# main_16.net
KiCad netlist of a schematic drawn in EAGLE
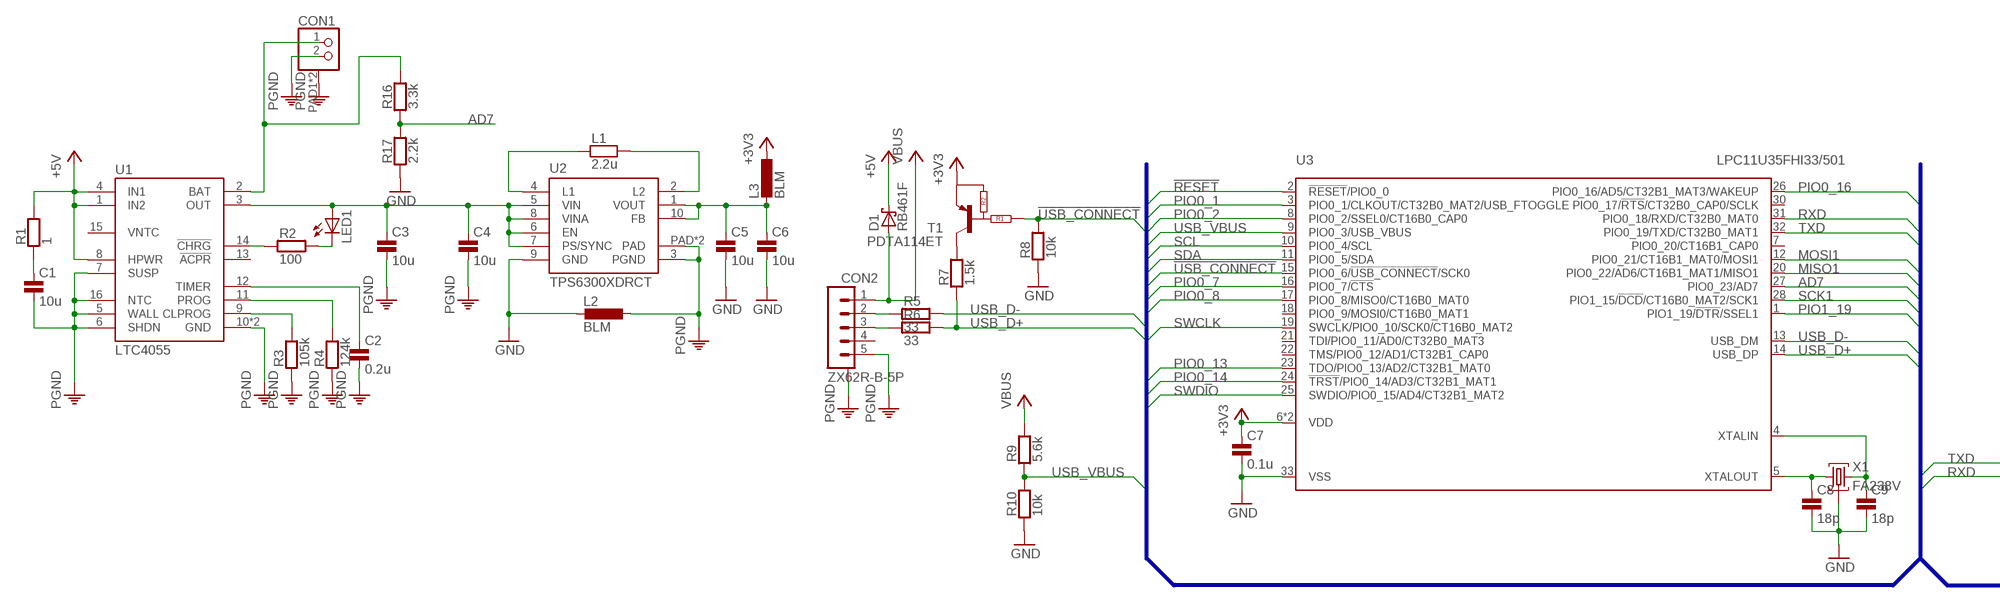
[diagram p0: schematic, sheet 1, part 1 of 2]
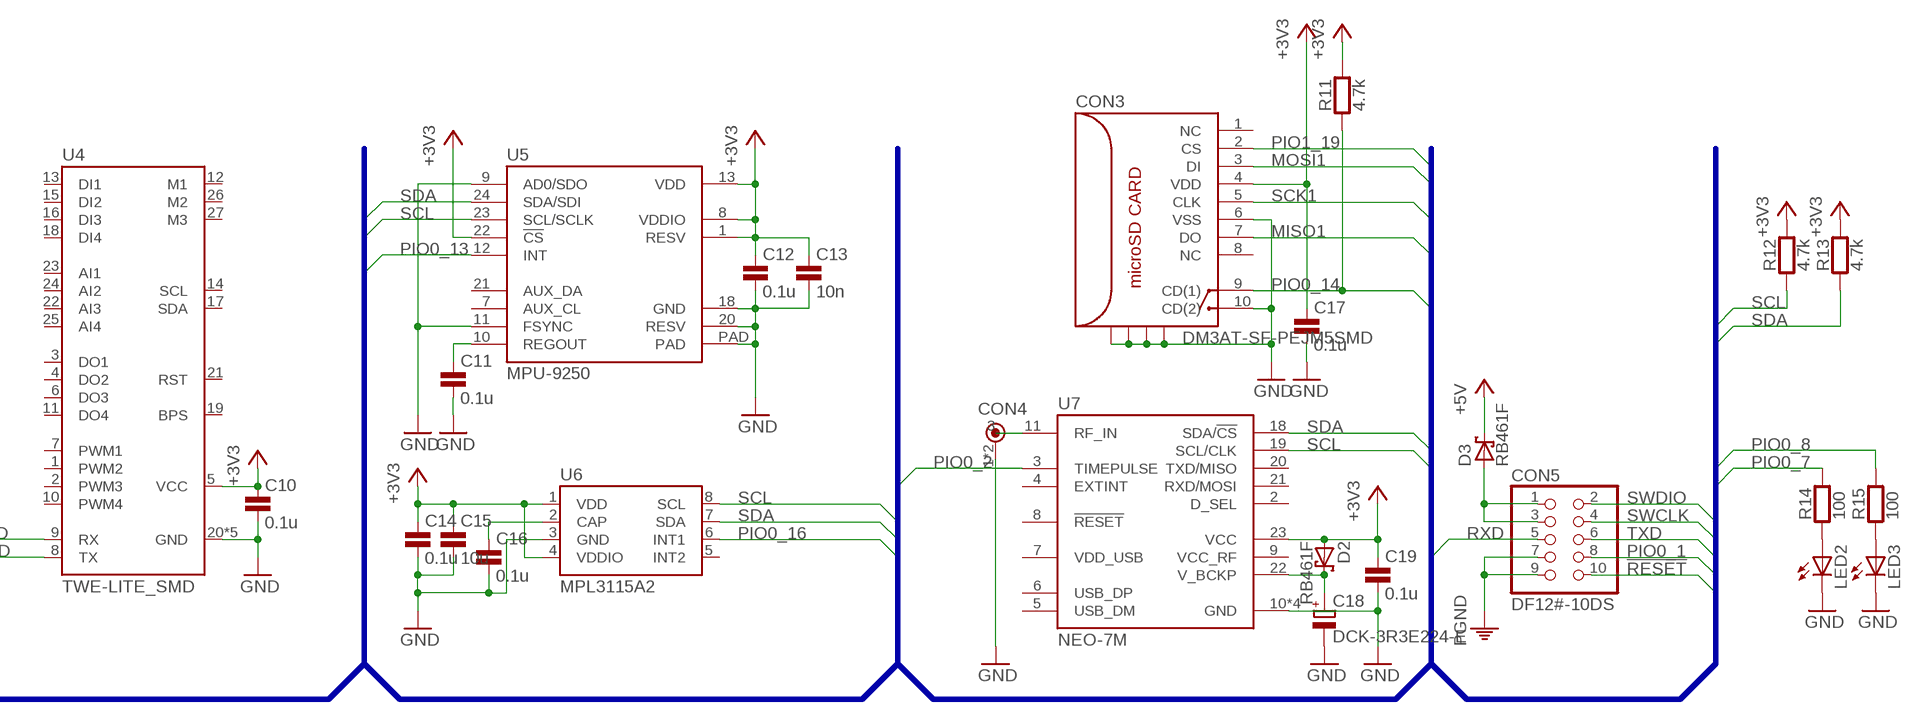
[diagram p1: schematic, sheet 1, part 2 of 2]

(export (version "E")
  (design (tool "Eeschema 10.0.6"))
  (components
    (comp (ref "C1")
      (value "10u")
      (footprint "eagle-import:0603")
      (libsource (lib "eagle-import") (part "C0603"))
    )
    (comp (ref "C2")
      (value "0.2u")
      (footprint "eagle-import:0402")
      (libsource (lib "eagle-import") (part "C0402"))
    )
    (comp (ref "C3")
      (value "10u")
      (footprint "eagle-import:0603")
      (libsource (lib "eagle-import") (part "C0603"))
    )
    (comp (ref "C4")
      (value "10u")
      (footprint "eagle-import:0603")
      (libsource (lib "eagle-import") (part "C0603"))
    )
    (comp (ref "C5")
      (value "10u")
      (footprint "eagle-import:0603")
      (libsource (lib "eagle-import") (part "C0603"))
    )
    (comp (ref "C6")
      (value "10u")
      (footprint "eagle-import:0603")
      (libsource (lib "eagle-import") (part "C0603"))
    )
    (comp (ref "C7")
      (value "0.1u")
      (footprint "eagle-import:0402")
      (libsource (lib "eagle-import") (part "C0402"))
    )
    (comp (ref "C8")
      (value "18p")
      (footprint "eagle-import:0402")
      (libsource (lib "eagle-import") (part "C0402"))
    )
    (comp (ref "C9")
      (value "18p")
      (footprint "eagle-import:0402")
      (libsource (lib "eagle-import") (part "C0402"))
    )
    (comp (ref "C10")
      (value "0.1u")
      (footprint "eagle-import:0402")
      (libsource (lib "eagle-import") (part "C0402"))
    )
    (comp (ref "C11")
      (value "0.1u")
      (footprint "eagle-import:0402")
      (libsource (lib "eagle-import") (part "C0402"))
    )
    (comp (ref "C12")
      (value "0.1u")
      (footprint "eagle-import:0402")
      (libsource (lib "eagle-import") (part "C0402"))
    )
    (comp (ref "C13")
      (value "10n")
      (footprint "eagle-import:0402")
      (libsource (lib "eagle-import") (part "C0402"))
    )
    (comp (ref "C14")
      (value "0.1u")
      (footprint "eagle-import:0402")
      (libsource (lib "eagle-import") (part "C0402"))
    )
    (comp (ref "C15")
      (value "10u")
      (footprint "eagle-import:0402")
      (libsource (lib "eagle-import") (part "C0402"))
    )
    (comp (ref "C16")
      (value "0.1u")
      (footprint "eagle-import:0402")
      (libsource (lib "eagle-import") (part "C0402"))
    )
    (comp (ref "C17")
      (value "0.1u")
      (footprint "eagle-import:0402")
      (libsource (lib "eagle-import") (part "C0402"))
    )
    (comp (ref "C18")
      (value "DCK-3R3E224-E")
      (footprint "eagle-import:DCK-3R3E224-E")
      (libsource (lib "eagle-import") (part "DCK-3R3E224-E"))
    )
    (comp (ref "C19")
      (value "0.1u")
      (footprint "eagle-import:0402")
      (libsource (lib "eagle-import") (part "C0402"))
    )
    (comp (ref "CON1")
      (value "JST-PH2")
      (footprint "eagle-import:JST-PH2")
      (libsource (lib "eagle-import") (part "JST-PH2"))
    )
    (comp (ref "CON2")
      (value "ZX62R-B-5P")
      (footprint "eagle-import:MICRO-B")
      (libsource (lib "eagle-import") (part "ZX62R-B-5P"))
    )
    (comp (ref "CON3")
      (value "DM3AT-SF-PEJM5SMD")
      (footprint "eagle-import:DM3AT-SF-PEJM5")
      (libsource (lib "eagle-import") (part "DM3AT-SF-PEJM5SMD"))
    )
    (comp (ref "CON4")
      (value "U.FL")
      (footprint "eagle-import:U.FL-R-SMT-1")
      (libsource (lib "eagle-import") (part "U.FL"))
    )
    (comp (ref "CON5")
      (value "DF12#-10DS")
      (footprint "eagle-import:DF12A-10DS")
      (libsource (lib "eagle-import") (part "DF12#-10DS"))
    )
    (comp (ref "D1")
      (value "RB461F")
      (footprint "eagle-import:UMD3")
      (libsource (lib "eagle-import") (part "RB461F"))
    )
    (comp (ref "D2")
      (value "RB461F")
      (footprint "eagle-import:UMD3")
      (libsource (lib "eagle-import") (part "RB461F"))
    )
    (comp (ref "D3")
      (value "RB461F")
      (footprint "eagle-import:UMD3")
      (libsource (lib "eagle-import") (part "RB461F"))
    )
    (comp (ref "L1")
      (value "2.2u")
      (footprint "eagle-import:VLF4012ST")
      (libsource (lib "eagle-import") (part "VLF4012ST"))
    )
    (comp (ref "L2")
      (value "BLM")
      (footprint "eagle-import:C0603K")
      (libsource (lib "eagle-import") (part "L-EU"))
    )
    (comp (ref "L3")
      (value "BLM")
      (footprint "eagle-import:C0603K")
      (libsource (lib "eagle-import") (part "L-EU"))
    )
    (comp (ref "LED1")
      (value "LEDSML0603")
      (footprint "eagle-import:SML0603")
      (libsource (lib "eagle-import") (part "LEDSML0603"))
    )
    (comp (ref "LED2")
      (value "LEDSML0603")
      (footprint "eagle-import:SML0603")
      (libsource (lib "eagle-import") (part "LEDSML0603"))
    )
    (comp (ref "LED3")
      (value "LEDSML0603")
      (footprint "eagle-import:SML0603")
      (libsource (lib "eagle-import") (part "LEDSML0603"))
    )
    (comp (ref "R1")
      (value "1")
      (footprint "eagle-import:0402")
      (libsource (lib "eagle-import") (part "R0402"))
    )
    (comp (ref "R2")
      (value "100")
      (footprint "eagle-import:0402")
      (libsource (lib "eagle-import") (part "R0402"))
    )
    (comp (ref "R3")
      (value "105k")
      (footprint "eagle-import:0402")
      (libsource (lib "eagle-import") (part "R0402"))
    )
    (comp (ref "R4")
      (value "124k")
      (footprint "eagle-import:0402")
      (libsource (lib "eagle-import") (part "R0402"))
    )
    (comp (ref "R5")
      (value "33")
      (footprint "eagle-import:0402")
      (libsource (lib "eagle-import") (part "R0402"))
    )
    (comp (ref "R6")
      (value "33")
      (footprint "eagle-import:0402")
      (libsource (lib "eagle-import") (part "R0402"))
    )
    (comp (ref "R7")
      (value "1.5k")
      (footprint "eagle-import:0402")
      (libsource (lib "eagle-import") (part "R0402"))
    )
    (comp (ref "R8")
      (value "10k")
      (footprint "eagle-import:0402")
      (libsource (lib "eagle-import") (part "R0402"))
    )
    (comp (ref "R9")
      (value "5.6k")
      (footprint "eagle-import:0402")
      (libsource (lib "eagle-import") (part "R0402"))
    )
    (comp (ref "R10")
      (value "10k")
      (footprint "eagle-import:0402")
      (libsource (lib "eagle-import") (part "R0402"))
    )
    (comp (ref "R11")
      (value "4.7k")
      (footprint "eagle-import:0402")
      (libsource (lib "eagle-import") (part "R0402"))
    )
    (comp (ref "R12")
      (value "4.7k")
      (footprint "eagle-import:0402")
      (libsource (lib "eagle-import") (part "R0402"))
    )
    (comp (ref "R13")
      (value "4.7k")
      (footprint "eagle-import:0402")
      (libsource (lib "eagle-import") (part "R0402"))
    )
    (comp (ref "R14")
      (value "100")
      (footprint "eagle-import:0402")
      (libsource (lib "eagle-import") (part "R0402"))
    )
    (comp (ref "R15")
      (value "100")
      (footprint "eagle-import:0402")
      (libsource (lib "eagle-import") (part "R0402"))
    )
    (comp (ref "R16")
      (value "3.3k")
      (footprint "eagle-import:0402")
      (libsource (lib "eagle-import") (part "R0402"))
    )
    (comp (ref "R17")
      (value "2.2k")
      (footprint "eagle-import:0402")
      (libsource (lib "eagle-import") (part "R0402"))
    )
    (comp (ref "T1")
      (value "PDTA114ET")
      (footprint "eagle-import:SOT23")
      (libsource (lib "eagle-import") (part "PDTA114TE"))
    )
    (comp (ref "U1")
      (value "LTC4055")
      (footprint "eagle-import:QFN16")
      (libsource (lib "eagle-import") (part "LTC4055"))
    )
    (comp (ref "U2")
      (value "TPS6300XDRCT")
      (footprint "eagle-import:S-PVSON-N10")
      (libsource (lib "eagle-import") (part "TPS6300XDRCT"))
    )
    (comp (ref "U3")
      (value "LPC11U35FHI33/501")
      (footprint "eagle-import:SOT617-3")
      (libsource (lib "eagle-import") (part "LPC11U35FHI33/501"))
    )
    (comp (ref "U4")
      (value "TWE-LITE_SMD")
      (footprint "eagle-import:LITE")
      (libsource (lib "eagle-import") (part "TWE-LITE_SMD"))
    )
    (comp (ref "U5")
      (value "MPU-9250")
      (footprint "eagle-import:MPU-9250")
      (libsource (lib "eagle-import") (part "MPU-9250"))
    )
    (comp (ref "U6")
      (value "MPL3115A2")
      (footprint "eagle-import:MPL3115A2")
      (libsource (lib "eagle-import") (part "MPL3115A2"))
    )
    (comp (ref "U7")
      (value "NEO-7M")
      (footprint "eagle-import:NEO-7M")
      (libsource (lib "eagle-import") (part "NEO-7M"))
    )
    (comp (ref "X1")
      (value "FA238V")
      (footprint "eagle-import:V66RA")
      (libsource (lib "eagle-import") (part "FA238V"))
    )
  )
  (nets
    (net (code "1") (name "+3V3") (class "Default")
      (node (ref "C10") (pin "1") (pinfunction "P$1_1") (pintype "passive"))
      (node (ref "C12") (pin "1") (pinfunction "P$1_1") (pintype "passive"))
      (node (ref "C13") (pin "1") (pinfunction "P$1_1") (pintype "passive"))
      (node (ref "C14") (pin "1") (pinfunction "P$1_1") (pintype "passive"))
      (node (ref "C15") (pin "1") (pinfunction "P$1_1") (pintype "passive"))
      (node (ref "C17") (pin "1") (pinfunction "P$1_1") (pintype "passive"))
      (node (ref "C19") (pin "1") (pinfunction "P$1_1") (pintype "passive"))
      (node (ref "C7") (pin "1") (pinfunction "P$1_1") (pintype "passive"))
      (node (ref "CON3") (pin "4") (pinfunction "VDD_4") (pintype "power_in"))
      (node (ref "D2") (pin "2") (pinfunction "A_2") (pintype "passive"))
      (node (ref "L3") (pin "1") (pinfunction "1_1") (pintype "passive"))
      (node (ref "R11") (pin "2") (pinfunction "P$2_2") (pintype "passive"))
      (node (ref "R12") (pin "2") (pinfunction "P$2_2") (pintype "passive"))
      (node (ref "R13") (pin "2") (pinfunction "P$2_2") (pintype "passive"))
      (node (ref "T1") (pin "2") (pinfunction "E_2") (pintype "passive"))
      (node (ref "U3") (pin "29") (pinfunction "VDD_29") (pintype "power_in"))
      (node (ref "U3") (pin "6") (pinfunction "VDD_6") (pintype "power_in"))
      (node (ref "U4") (pin "5") (pinfunction "VCC_5") (pintype "power_in"))
      (node (ref "U5") (pin "1") (pinfunction "RESV_1") (pintype "passive"))
      (node (ref "U5") (pin "13") (pinfunction "VDD_13") (pintype "power_in"))
      (node (ref "U5") (pin "22") (pinfunction "~{CS}_22") (pintype "input"))
      (node (ref "U5") (pin "8") (pinfunction "VDDIO_8") (pintype "power_in"))
      (node (ref "U6") (pin "1") (pinfunction "VDD_1") (pintype "power_in"))
      (node (ref "U6") (pin "4") (pinfunction "VDDIO_4") (pintype "input"))
      (node (ref "U7") (pin "23") (pinfunction "VCC_23") (pintype "power_in"))
    )
    (net (code "2") (name "+5V") (class "Default")
      (node (ref "D1") (pin "3") (pinfunction "C_3") (pintype "passive"))
      (node (ref "D3") (pin "3") (pinfunction "C_3") (pintype "passive"))
      (node (ref "R1") (pin "2") (pinfunction "P$2_2") (pintype "passive"))
      (node (ref "U1") (pin "1") (pinfunction "IN2_1") (pintype "power_in"))
      (node (ref "U1") (pin "4") (pinfunction "IN1_4") (pintype "power_in"))
      (node (ref "U1") (pin "8") (pinfunction "HPWR_8") (pintype "input"))
    )
    (net (code "3") (name "/AD7") (class "Default")
      (node (ref "R16") (pin "1") (pinfunction "P$1_1") (pintype "passive"))
      (node (ref "R17") (pin "2") (pinfunction "P$2_2") (pintype "passive"))
      (node (ref "U3") (pin "27") (pinfunction "PIO0_23/AD7_27") (pintype "bidirectional"))
    )
    (net (code "4") (name "/MISO1") (class "Default")
      (node (ref "CON3") (pin "7") (pinfunction "DO_7") (pintype "output"))
      (node (ref "U3") (pin "20") (pinfunction "PIO0_22/AD6/CT16B1_MAT1/MISO1_20") (pintype "bidirectional"))
    )
    (net (code "5") (name "/MOSI1") (class "Default")
      (node (ref "CON3") (pin "3") (pinfunction "DI_3") (pintype "input"))
      (node (ref "U3") (pin "12") (pinfunction "PIO0_21/CT16B1_MAT0/MOSI1_12") (pintype "bidirectional"))
    )
    (net (code "6") (name "/PIO0_1") (class "Default")
      (node (ref "CON5") (pin "8") (pinfunction "8_8") (pintype "passive"))
      (node (ref "U3") (pin "3") (pinfunction "PIO0_1/CLKOUT/CT32B0_MAT2/USB_FTOGGLE_3") (pintype "bidirectional"))
    )
    (net (code "7") (name "/PIO0_2") (class "Default")
      (node (ref "U3") (pin "8") (pinfunction "PIO0_2/SSEL0/CT16B0_CAP0_8") (pintype "bidirectional"))
      (node (ref "U7") (pin "3") (pinfunction "TIMEPULSE_3") (pintype "output"))
    )
    (net (code "8") (name "/PIO0_7") (class "Default")
      (node (ref "R14") (pin "2") (pinfunction "P$2_2") (pintype "passive"))
      (node (ref "U3") (pin "16") (pinfunction "PIO0_7/~{CTS}_16") (pintype "bidirectional"))
    )
    (net (code "9") (name "/PIO0_8") (class "Default")
      (node (ref "R15") (pin "2") (pinfunction "P$2_2") (pintype "passive"))
      (node (ref "U3") (pin "17") (pinfunction "PIO0_8/MISO0/CT16B0_MAT0_17") (pintype "bidirectional"))
    )
    (net (code "10") (name "/PIO0_13") (class "Default")
      (node (ref "U3") (pin "23") (pinfunction "TDO/PIO0_13/AD2/CT32B1_MAT0_23") (pintype "bidirectional"))
      (node (ref "U5") (pin "12") (pinfunction "INT_12") (pintype "output"))
    )
    (net (code "11") (name "/PIO0_14") (class "Default")
      (node (ref "CON3") (pin "9") (pinfunction "CD(1)_9") (pintype "bidirectional"))
      (node (ref "R11") (pin "1") (pinfunction "P$1_1") (pintype "passive"))
      (node (ref "U3") (pin "24") (pinfunction "~{TRST}/PIO0_14/AD3/CT32B1_MAT1_24") (pintype "bidirectional"))
    )
    (net (code "12") (name "/PIO0_16") (class "Default")
      (node (ref "U3") (pin "26") (pinfunction "PIO0_16/AD5/CT32B1_MAT3/WAKEUP_26") (pintype "bidirectional"))
      (node (ref "U6") (pin "6") (pinfunction "INT1_6") (pintype "output"))
    )
    (net (code "13") (name "/PIO1_19") (class "Default")
      (node (ref "CON3") (pin "2") (pinfunction "CS_2") (pintype "input"))
      (node (ref "U3") (pin "1") (pinfunction "PIO1_19/~{DTR}/SSEL1_1") (pintype "bidirectional"))
    )
    (net (code "14") (name "/RXD") (class "Default")
      (node (ref "CON5") (pin "5") (pinfunction "5_5") (pintype "passive"))
      (node (ref "U3") (pin "31") (pinfunction "PIO0_18/RXD/CT32B0_MAT0_31") (pintype "bidirectional"))
      (node (ref "U4") (pin "8") (pinfunction "TX_8") (pintype "output"))
    )
    (net (code "15") (name "/SCK1") (class "Default")
      (node (ref "CON3") (pin "5") (pinfunction "CLK_5") (pintype "input"))
      (node (ref "U3") (pin "28") (pinfunction "PIO1_15/~{DCD}/CT16B0_MAT2/SCK1_28") (pintype "bidirectional"))
    )
    (net (code "16") (name "/SCL") (class "Default")
      (node (ref "R12") (pin "1") (pinfunction "P$1_1") (pintype "passive"))
      (node (ref "U3") (pin "10") (pinfunction "PIO0_4/SCL_10") (pintype "bidirectional"))
      (node (ref "U5") (pin "23") (pinfunction "SCL/SCLK_23") (pintype "input"))
      (node (ref "U6") (pin "8") (pinfunction "SCL_8") (pintype "input"))
      (node (ref "U7") (pin "19") (pinfunction "SCL/CLK_19") (pintype "input"))
    )
    (net (code "17") (name "/SDA") (class "Default")
      (node (ref "R13") (pin "1") (pinfunction "P$1_1") (pintype "passive"))
      (node (ref "U3") (pin "11") (pinfunction "PIO0_5/SDA_11") (pintype "bidirectional"))
      (node (ref "U5") (pin "24") (pinfunction "SDA/SDI_24") (pintype "bidirectional"))
      (node (ref "U6") (pin "7") (pinfunction "SDA_7") (pintype "bidirectional"))
      (node (ref "U7") (pin "18") (pinfunction "SDA/~{CS}_18") (pintype "bidirectional"))
    )
    (net (code "18") (name "/SWCLK") (class "Default")
      (node (ref "CON5") (pin "4") (pinfunction "4_4") (pintype "passive"))
      (node (ref "U3") (pin "19") (pinfunction "SWCLK/PIO0_10/SCK0/CT16B0_MAT2_19") (pintype "bidirectional"))
    )
    (net (code "19") (name "/SWDIO") (class "Default")
      (node (ref "CON5") (pin "2") (pinfunction "2_2") (pintype "passive"))
      (node (ref "U3") (pin "25") (pinfunction "SWDIO/PIO0_15/AD4/CT32B1_MAT2_25") (pintype "bidirectional"))
    )
    (net (code "20") (name "/TXD") (class "Default")
      (node (ref "CON5") (pin "6") (pinfunction "6_6") (pintype "passive"))
      (node (ref "U3") (pin "32") (pinfunction "PIO0_19/TXD/CT32B0_MAT1_32") (pintype "bidirectional"))
      (node (ref "U4") (pin "9") (pinfunction "RX_9") (pintype "input"))
    )
    (net (code "21") (name "/USB_D+") (class "Default")
      (node (ref "R6") (pin "2") (pinfunction "P$2_2") (pintype "passive"))
      (node (ref "R7") (pin "1") (pinfunction "P$1_1") (pintype "passive"))
      (node (ref "U3") (pin "14") (pinfunction "USB_DP_14") (pintype "bidirectional"))
    )
    (net (code "22") (name "/USB_D-") (class "Default")
      (node (ref "R5") (pin "2") (pinfunction "P$2_2") (pintype "passive"))
      (node (ref "U3") (pin "13") (pinfunction "USB_DM_13") (pintype "bidirectional"))
    )
    (net (code "23") (name "/USB_VBUS") (class "Default")
      (node (ref "R10") (pin "2") (pinfunction "P$2_2") (pintype "passive"))
      (node (ref "R9") (pin "1") (pinfunction "P$1_1") (pintype "passive"))
      (node (ref "U3") (pin "9") (pinfunction "PIO0_3/USB_VBUS_9") (pintype "bidirectional"))
    )
    (net (code "24") (name "/VDD_USB") (class "Default")
      (node (ref "U7") (pin "7") (pinfunction "VDD_USB_7") (pintype "power_in"))
    )
    (net (code "25") (name "/VNTC") (class "Default")
      (node (ref "U1") (pin "15") (pinfunction "VNTC_15") (pintype "power_in"))
    )
    (net (code "26") (name "/~{RESET}") (class "Default")
      (node (ref "CON5") (pin "10") (pinfunction "10_10") (pintype "passive"))
      (node (ref "U3") (pin "2") (pinfunction "~{RESET}/PIO0_0_2") (pintype "bidirectional"))
    )
    (net (code "27") (name "/~{USB_CONNECT}") (class "Default")
      (node (ref "R8") (pin "2") (pinfunction "P$2_2") (pintype "passive"))
      (node (ref "T1") (pin "1") (pinfunction "INPUT_1") (pintype "passive"))
      (node (ref "U3") (pin "15") (pinfunction "PIO0_6/~{USB_CONNECT}/SCK0_15") (pintype "bidirectional"))
    )
    (net (code "28") (name "GND") (class "Default")
      (node (ref "C10") (pin "2") (pinfunction "P$2_2") (pintype "passive"))
      (node (ref "C11") (pin "2") (pinfunction "P$2_2") (pintype "passive"))
      (node (ref "C12") (pin "2") (pinfunction "P$2_2") (pintype "passive"))
      (node (ref "C13") (pin "2") (pinfunction "P$2_2") (pintype "passive"))
      (node (ref "C14") (pin "2") (pinfunction "P$2_2") (pintype "passive"))
      (node (ref "C15") (pin "2") (pinfunction "P$2_2") (pintype "passive"))
      (node (ref "C16") (pin "2") (pinfunction "P$2_2") (pintype "passive"))
      (node (ref "C17") (pin "2") (pinfunction "P$2_2") (pintype "passive"))
      (node (ref "C18") (pin "1") (pinfunction "-_1") (pintype "passive"))
      (node (ref "C19") (pin "2") (pinfunction "P$2_2") (pintype "passive"))
      (node (ref "C5") (pin "2") (pinfunction "P$2_2") (pintype "passive"))
      (node (ref "C6") (pin "2") (pinfunction "P$2_2") (pintype "passive"))
      (node (ref "C7") (pin "2") (pinfunction "P$2_2") (pintype "passive"))
      (node (ref "C8") (pin "2") (pinfunction "P$2_2") (pintype "passive"))
      (node (ref "C9") (pin "2") (pinfunction "P$2_2") (pintype "passive"))
      (node (ref "CON3") (pin "10") (pinfunction "CD(2)_10") (pintype "bidirectional"))
      (node (ref "CON3") (pin "6") (pinfunction "VSS_6") (pintype "power_in"))
      (node (ref "CON3") (pin "P$10") (pinfunction "P$1_P$10") (pintype "passive"))
      (node (ref "CON3") (pin "P$11") (pinfunction "P$2_P$11") (pintype "passive"))
      (node (ref "CON3") (pin "P$12") (pinfunction "P$3_P$12") (pintype "passive"))
      (node (ref "CON3") (pin "P$14") (pinfunction "P$4_P$14") (pintype "passive"))
      (node (ref "CON4") (pin "1") (pinfunction "GND_1") (pintype "power_in"))
      (node (ref "CON4") (pin "2") (pinfunction "GND_2") (pintype "power_in"))
      (node (ref "L2") (pin "2") (pinfunction "2_2") (pintype "passive"))
      (node (ref "LED2") (pin "C") (pinfunction "C_C") (pintype "passive"))
      (node (ref "LED3") (pin "C") (pinfunction "C_C") (pintype "passive"))
      (node (ref "R10") (pin "1") (pinfunction "P$1_1") (pintype "passive"))
      (node (ref "R17") (pin "1") (pinfunction "P$1_1") (pintype "passive"))
      (node (ref "R8") (pin "1") (pinfunction "P$1_1") (pintype "passive"))
      (node (ref "U2") (pin "9") (pinfunction "GND_9") (pintype "power_in"))
      (node (ref "U3") (pin "33") (pinfunction "VSS_33") (pintype "power_in"))
      (node (ref "U4") (pin "20") (pinfunction "GND_20") (pintype "power_in"))
      (node (ref "U4") (pin "28") (pinfunction "GND_28") (pintype "power_in"))
      (node (ref "U4") (pin "30") (pinfunction "GND_30") (pintype "power_in"))
      (node (ref "U4") (pin "31") (pinfunction "GND_31") (pintype "power_in"))
      (node (ref "U4") (pin "32") (pinfunction "GND_32") (pintype "power_in"))
      (node (ref "U5") (pin "11") (pinfunction "FSYNC_11") (pintype "input"))
      (node (ref "U5") (pin "18") (pinfunction "GND_18") (pintype "power_in"))
      (node (ref "U5") (pin "20") (pinfunction "RESV_20") (pintype "passive"))
      (node (ref "U5") (pin "9") (pinfunction "AD0/SDO_9") (pintype "bidirectional"))
      (node (ref "U5") (pin "PAD") (pinfunction "PAD_PAD") (pintype "passive"))
      (node (ref "U6") (pin "3") (pinfunction "GND_3") (pintype "power_in"))
      (node (ref "U7") (pin "10") (pinfunction "GND_10") (pintype "power_in"))
      (node (ref "U7") (pin "12") (pinfunction "GND_12") (pintype "power_in"))
      (node (ref "U7") (pin "13") (pinfunction "GND_13") (pintype "power_in"))
      (node (ref "U7") (pin "24") (pinfunction "GND_24") (pintype "power_in"))
      (node (ref "X1") (pin "P2GND") (pinfunction "GND_P2GND") (pintype "power_in"))
      (node (ref "X1") (pin "P4GND") (pinfunction "GND_P4GND") (pintype "power_in"))
    )
    (net (code "29") (name "Net-(C1-P$1)") (class "Default")
      (node (ref "C1") (pin "1") (pinfunction "P$1_1") (pintype "passive"))
      (node (ref "R1") (pin "1") (pinfunction "P$1_1") (pintype "passive"))
    )
    (net (code "30") (name "Net-(C2-P$1)") (class "Default")
      (node (ref "C2") (pin "1") (pinfunction "P$1_1") (pintype "passive"))
      (node (ref "U1") (pin "12") (pinfunction "TIMER_12") (pintype "passive"))
    )
    (net (code "31") (name "Net-(C3-P$1)") (class "Default")
      (node (ref "C3") (pin "1") (pinfunction "P$1_1") (pintype "passive"))
      (node (ref "C4") (pin "1") (pinfunction "P$1_1") (pintype "passive"))
      (node (ref "LED1") (pin "A") (pinfunction "A_A") (pintype "passive"))
      (node (ref "U1") (pin "3") (pinfunction "OUT_3") (pintype "power_in"))
      (node (ref "U2") (pin "5") (pinfunction "VIN_5") (pintype "power_in"))
      (node (ref "U2") (pin "6") (pinfunction "EN_6") (pintype "input"))
      (node (ref "U2") (pin "7") (pinfunction "PS/SYNC_7") (pintype "input"))
      (node (ref "U2") (pin "8") (pinfunction "VINA_8") (pintype "power_in"))
    )
    (net (code "32") (name "Net-(C5-P$1)") (class "Default")
      (node (ref "C5") (pin "1") (pinfunction "P$1_1") (pintype "passive"))
      (node (ref "C6") (pin "1") (pinfunction "P$1_1") (pintype "passive"))
      (node (ref "L3") (pin "2") (pinfunction "2_2") (pintype "passive"))
      (node (ref "U2") (pin "1") (pinfunction "VOUT_1") (pintype "output"))
      (node (ref "U2") (pin "10") (pinfunction "FB_10") (pintype "input"))
    )
    (net (code "33") (name "Net-(C8-P$1)") (class "Default")
      (node (ref "C8") (pin "1") (pinfunction "P$1_1") (pintype "passive"))
      (node (ref "U3") (pin "5") (pinfunction "XTALOUT_5") (pintype "output"))
      (node (ref "X1") (pin "P1X1") (pinfunction "X1_P1X1") (pintype "output"))
    )
    (net (code "34") (name "Net-(C9-P$1)") (class "Default")
      (node (ref "C9") (pin "1") (pinfunction "P$1_1") (pintype "passive"))
      (node (ref "U3") (pin "4") (pinfunction "XTALIN_4") (pintype "input"))
      (node (ref "X1") (pin "P3X2") (pinfunction "X2_P3X2") (pintype "output"))
    )
    (net (code "35") (name "Net-(C11-P$1)") (class "Default")
      (node (ref "C11") (pin "1") (pinfunction "P$1_1") (pintype "passive"))
      (node (ref "U5") (pin "10") (pinfunction "REGOUT_10") (pintype "passive"))
    )
    (net (code "36") (name "Net-(C16-P$1)") (class "Default")
      (node (ref "C16") (pin "1") (pinfunction "P$1_1") (pintype "passive"))
      (node (ref "U6") (pin "2") (pinfunction "CAP_2") (pintype "passive"))
    )
    (net (code "37") (name "Net-(C18-+)") (class "Default")
      (node (ref "C18") (pin "2") (pinfunction "+_2") (pintype "passive"))
      (node (ref "D2") (pin "3") (pinfunction "C_3") (pintype "passive"))
      (node (ref "U7") (pin "22") (pinfunction "V_BCKP_22") (pintype "power_in"))
    )
    (net (code "38") (name "Net-(CON2-2.D-)") (class "Default")
      (node (ref "CON2") (pin "2") (pinfunction "2.D-_2") (pintype "passive"))
      (node (ref "R5") (pin "1") (pinfunction "P$1_1") (pintype "passive"))
    )
    (net (code "39") (name "Net-(CON2-3.D+)") (class "Default")
      (node (ref "CON2") (pin "3") (pinfunction "3.D+_3") (pintype "passive"))
      (node (ref "R6") (pin "1") (pinfunction "P$1_1") (pintype "passive"))
    )
    (net (code "40") (name "Net-(CON4-RF)") (class "Default")
      (node (ref "CON4") (pin "3") (pinfunction "RF_3") (pintype "output"))
      (node (ref "U7") (pin "11") (pinfunction "RF_IN_11") (pintype "input"))
    )
    (net (code "41") (name "Net-(D3-A)") (class "Default")
      (node (ref "CON5") (pin "1") (pinfunction "1_1") (pintype "passive"))
      (node (ref "CON5") (pin "3") (pinfunction "3_3") (pintype "passive"))
      (node (ref "D3") (pin "2") (pinfunction "A_2") (pintype "passive"))
    )
    (net (code "42") (name "Net-(R2-P$1)") (class "Default")
      (node (ref "R2") (pin "1") (pinfunction "P$1_1") (pintype "passive"))
      (node (ref "U1") (pin "14") (pinfunction "~{CHRG}_14") (pintype "tri_state"))
    )
    (net (code "43") (name "Net-(R2-P$2)") (class "Default")
      (node (ref "LED1") (pin "C") (pinfunction "C_C") (pintype "passive"))
      (node (ref "R2") (pin "2") (pinfunction "P$2_2") (pintype "passive"))
    )
    (net (code "44") (name "Net-(R3-P$2)") (class "Default")
      (node (ref "R3") (pin "2") (pinfunction "P$2_2") (pintype "passive"))
      (node (ref "U1") (pin "9") (pinfunction "CLPROG_9") (pintype "passive"))
    )
    (net (code "45") (name "Net-(R4-P$2)") (class "Default")
      (node (ref "R4") (pin "2") (pinfunction "P$2_2") (pintype "passive"))
      (node (ref "U1") (pin "11") (pinfunction "PROG_11") (pintype "passive"))
    )
    (net (code "46") (name "Net-(R7-P$2)") (class "Default")
      (node (ref "R7") (pin "2") (pinfunction "P$2_2") (pintype "passive"))
      (node (ref "T1") (pin "3") (pinfunction "C_3") (pintype "passive"))
    )
    (net (code "47") (name "Net-(R14-P$1)") (class "Default")
      (node (ref "LED2") (pin "A") (pinfunction "A_A") (pintype "passive"))
      (node (ref "R14") (pin "1") (pinfunction "P$1_1") (pintype "passive"))
    )
    (net (code "48") (name "Net-(R15-P$1)") (class "Default")
      (node (ref "LED3") (pin "A") (pinfunction "A_A") (pintype "passive"))
      (node (ref "R15") (pin "1") (pinfunction "P$1_1") (pintype "passive"))
    )
    (net (code "49") (name "Net-(R16-P$2)") (class "Default")
      (node (ref "CON1") (pin "1") (pinfunction "1_1") (pintype "passive"))
      (node (ref "R16") (pin "2") (pinfunction "P$2_2") (pintype "passive"))
      (node (ref "U1") (pin "2") (pinfunction "BAT_2") (pintype "power_in"))
    )
    (net (code "50") (name "Net-(U2-L1)") (class "Default")
      (node (ref "L1") (pin "1") (pinfunction "1_1") (pintype "passive"))
      (node (ref "U2") (pin "4") (pinfunction "L1_4") (pintype "bidirectional"))
    )
    (net (code "51") (name "Net-(U2-L2)") (class "Default")
      (node (ref "L1") (pin "2") (pinfunction "2_2") (pintype "passive"))
      (node (ref "U2") (pin "2") (pinfunction "L2_2") (pintype "bidirectional"))
    )
    (net (code "52") (name "PGND") (class "Default")
      (node (ref "C1") (pin "2") (pinfunction "P$2_2") (pintype "passive"))
      (node (ref "C2") (pin "2") (pinfunction "P$2_2") (pintype "passive"))
      (node (ref "C3") (pin "2") (pinfunction "P$2_2") (pintype "passive"))
      (node (ref "C4") (pin "2") (pinfunction "P$2_2") (pintype "passive"))
      (node (ref "CON1") (pin "2") (pinfunction "2_2") (pintype "passive"))
      (node (ref "CON1") (pin "PAD1") (pinfunction "P$1_PAD1") (pintype "power_in"))
      (node (ref "CON1") (pin "PAD2") (pinfunction "P$1_PAD2") (pintype "power_in"))
      (node (ref "CON2") (pin "5") (pinfunction "5.GND_5") (pintype "passive"))
      (node (ref "CON2") (pin "CASE@1") (pinfunction "P$1_CASE@1") (pintype "bidirectional"))
      (node (ref "CON2") (pin "CASE@2") (pinfunction "P$1_CASE@2") (pintype "bidirectional"))
      (node (ref "CON2") (pin "CASE@3") (pinfunction "P$1_CASE@3") (pintype "bidirectional"))
      (node (ref "CON2") (pin "CASE@4") (pinfunction "P$1_CASE@4") (pintype "bidirectional"))
      (node (ref "CON5") (pin "7") (pinfunction "7_7") (pintype "passive"))
      (node (ref "CON5") (pin "9") (pinfunction "9_9") (pintype "passive"))
      (node (ref "L2") (pin "1") (pinfunction "1_1") (pintype "passive"))
      (node (ref "R3") (pin "1") (pinfunction "P$1_1") (pintype "passive"))
      (node (ref "R4") (pin "1") (pinfunction "P$1_1") (pintype "passive"))
      (node (ref "U1") (pin "10") (pinfunction "GND_10") (pintype "power_in"))
      (node (ref "U1") (pin "16") (pinfunction "NTC_16") (pintype "input"))
      (node (ref "U1") (pin "5") (pinfunction "WALL_5") (pintype "input"))
      (node (ref "U1") (pin "6") (pinfunction "SHDN_6") (pintype "input"))
      (node (ref "U1") (pin "7") (pinfunction "SUSP_7") (pintype "input"))
      (node (ref "U1") (pin "PAD") (pinfunction "GND_PAD") (pintype "power_in"))
      (node (ref "U2") (pin "3") (pinfunction "PGND_3") (pintype "power_in"))
      (node (ref "U2") (pin "PAD") (pinfunction "PAD_PAD") (pintype "power_in"))
      (node (ref "U2") (pin "PAD@1") (pinfunction "PAD_PAD@1") (pintype "power_in"))
    )
    (net (code "53") (name "VBUS") (class "Default")
      (node (ref "CON2") (pin "1") (pinfunction "1.VBUS_1") (pintype "passive"))
      (node (ref "D1") (pin "2") (pinfunction "A_2") (pintype "passive"))
      (node (ref "R9") (pin "2") (pinfunction "P$2_2") (pintype "passive"))
    )
    (net (code "54") (name "unconnected-(CON2-4.ID-Pad4)") (class "Default")
      (node (ref "CON2") (pin "4") (pinfunction "4.ID_4") (pintype "passive"))
    )
    (net (code "55") (name "unconnected-(CON3-NC-Pad1)") (class "Default")
      (node (ref "CON3") (pin "1") (pinfunction "NC_1") (pintype "no_connect"))
    )
    (net (code "56") (name "unconnected-(CON3-NC-Pad8)") (class "Default")
      (node (ref "CON3") (pin "8") (pinfunction "NC_8") (pintype "no_connect"))
    )
    (net (code "57") (name "unconnected-(U1-~{ACPR}-Pad13)") (class "Default")
      (node (ref "U1") (pin "13") (pinfunction "~{ACPR}_13") (pintype "tri_state"))
    )
    (net (code "58") (name "unconnected-(U3-PIO0_9{slash}MOSI0{slash}CT16B0_MAT1-Pad18)") (class "Default")
      (node (ref "U3") (pin "18") (pinfunction "PIO0_9/MOSI0/CT16B0_MAT1_18") (pintype "bidirectional"))
    )
    (net (code "59") (name "unconnected-(U3-PIO0_17{slash}~{RTS}{slash}CT32B0_CAP0{slash}SCLK-Pad30)") (class "Default")
      (node (ref "U3") (pin "30") (pinfunction "PIO0_17/~{RTS}/CT32B0_CAP0/SCLK_30") (pintype "bidirectional"))
    )
    (net (code "60") (name "unconnected-(U3-PIO0_20{slash}CT16B1_CAP0-Pad7)") (class "Default")
      (node (ref "U3") (pin "7") (pinfunction "PIO0_20/CT16B1_CAP0_7") (pintype "bidirectional"))
    )
    (net (code "61") (name "unconnected-(U3-TDI{slash}PIO0_11{slash}AD0{slash}CT32B0_MAT3-Pad21)") (class "Default")
      (node (ref "U3") (pin "21") (pinfunction "TDI/PIO0_11/AD0/CT32B0_MAT3_21") (pintype "bidirectional"))
    )
    (net (code "62") (name "unconnected-(U3-TMS{slash}PIO0_12{slash}AD1{slash}CT32B1_CAP0-Pad22)") (class "Default")
      (node (ref "U3") (pin "22") (pinfunction "TMS/PIO0_12/AD1/CT32B1_CAP0_22") (pintype "bidirectional"))
    )
    (net (code "63") (name "unconnected-(U4-AI1-Pad23)") (class "Default")
      (node (ref "U4") (pin "23") (pinfunction "AI1_23") (pintype "input"))
    )
    (net (code "64") (name "unconnected-(U4-AI2-Pad24)") (class "Default")
      (node (ref "U4") (pin "24") (pinfunction "AI2_24") (pintype "input"))
    )
    (net (code "65") (name "unconnected-(U4-AI3-Pad22)") (class "Default")
      (node (ref "U4") (pin "22") (pinfunction "AI3_22") (pintype "input"))
    )
    (net (code "66") (name "unconnected-(U4-AI4-Pad25)") (class "Default")
      (node (ref "U4") (pin "25") (pinfunction "AI4_25") (pintype "input"))
    )
    (net (code "67") (name "unconnected-(U4-BPS-Pad19)") (class "Default")
      (node (ref "U4") (pin "19") (pinfunction "BPS_19") (pintype "input"))
    )
    (net (code "68") (name "unconnected-(U4-DI1-Pad13)") (class "Default")
      (node (ref "U4") (pin "13") (pinfunction "DI1_13") (pintype "input"))
    )
    (net (code "69") (name "unconnected-(U4-DI2-Pad15)") (class "Default")
      (node (ref "U4") (pin "15") (pinfunction "DI2_15") (pintype "input"))
    )
    (net (code "70") (name "unconnected-(U4-DI3-Pad16)") (class "Default")
      (node (ref "U4") (pin "16") (pinfunction "DI3_16") (pintype "input"))
    )
    (net (code "71") (name "unconnected-(U4-DI4-Pad18)") (class "Default")
      (node (ref "U4") (pin "18") (pinfunction "DI4_18") (pintype "input"))
    )
    (net (code "72") (name "unconnected-(U4-DO1-Pad3)") (class "Default")
      (node (ref "U4") (pin "3") (pinfunction "DO1_3") (pintype "output"))
    )
    (net (code "73") (name "unconnected-(U4-DO2-Pad4)") (class "Default")
      (node (ref "U4") (pin "4") (pinfunction "DO2_4") (pintype "output"))
    )
    (net (code "74") (name "unconnected-(U4-DO3-Pad6)") (class "Default")
      (node (ref "U4") (pin "6") (pinfunction "DO3_6") (pintype "output"))
    )
    (net (code "75") (name "unconnected-(U4-DO4-Pad11)") (class "Default")
      (node (ref "U4") (pin "11") (pinfunction "DO4_11") (pintype "output"))
    )
    (net (code "76") (name "unconnected-(U4-M1-Pad12)") (class "Default")
      (node (ref "U4") (pin "12") (pinfunction "M1_12") (pintype "input"))
    )
    (net (code "77") (name "unconnected-(U4-M2-Pad26)") (class "Default")
      (node (ref "U4") (pin "26") (pinfunction "M2_26") (pintype "input"))
    )
    (net (code "78") (name "unconnected-(U4-M3-Pad27)") (class "Default")
      (node (ref "U4") (pin "27") (pinfunction "M3_27") (pintype "input"))
    )
    (net (code "79") (name "unconnected-(U4-PWM1-Pad7)") (class "Default")
      (node (ref "U4") (pin "7") (pinfunction "PWM1_7") (pintype "output"))
    )
    (net (code "80") (name "unconnected-(U4-PWM2-Pad1)") (class "Default")
      (node (ref "U4") (pin "1") (pinfunction "PWM2_1") (pintype "output"))
    )
    (net (code "81") (name "unconnected-(U4-PWM3-Pad2)") (class "Default")
      (node (ref "U4") (pin "2") (pinfunction "PWM3_2") (pintype "output"))
    )
    (net (code "82") (name "unconnected-(U4-PWM4-Pad10)") (class "Default")
      (node (ref "U4") (pin "10") (pinfunction "PWM4_10") (pintype "output"))
    )
    (net (code "83") (name "unconnected-(U4-RST-Pad21)") (class "Default")
      (node (ref "U4") (pin "21") (pinfunction "RST_21") (pintype "input"))
    )
    (net (code "84") (name "unconnected-(U4-SCL-Pad14)") (class "Default")
      (node (ref "U4") (pin "14") (pinfunction "SCL_14") (pintype "bidirectional"))
    )
    (net (code "85") (name "unconnected-(U4-SDA-Pad17)") (class "Default")
      (node (ref "U4") (pin "17") (pinfunction "SDA_17") (pintype "bidirectional"))
    )
    (net (code "86") (name "unconnected-(U5-AUX_CL-Pad7)") (class "Default")
      (node (ref "U5") (pin "7") (pinfunction "AUX_CL_7") (pintype "output"))
    )
    (net (code "87") (name "unconnected-(U5-AUX_DA-Pad21)") (class "Default")
      (node (ref "U5") (pin "21") (pinfunction "AUX_DA_21") (pintype "bidirectional"))
    )
    (net (code "88") (name "unconnected-(U6-INT2-Pad5)") (class "Default")
      (node (ref "U6") (pin "5") (pinfunction "INT2_5") (pintype "output"))
    )
    (net (code "89") (name "unconnected-(U7-D_SEL-Pad2)") (class "Default")
      (node (ref "U7") (pin "2") (pinfunction "D_SEL_2") (pintype "input"))
    )
    (net (code "90") (name "unconnected-(U7-EXTINT-Pad4)") (class "Default")
      (node (ref "U7") (pin "4") (pinfunction "EXTINT_4") (pintype "input"))
    )
    (net (code "91") (name "unconnected-(U7-RXD{slash}MOSI-Pad21)") (class "Default")
      (node (ref "U7") (pin "21") (pinfunction "RXD/MOSI_21") (pintype "input"))
    )
    (net (code "92") (name "unconnected-(U7-TXD{slash}MISO-Pad20)") (class "Default")
      (node (ref "U7") (pin "20") (pinfunction "TXD/MISO_20") (pintype "output"))
    )
    (net (code "93") (name "unconnected-(U7-USB_DM-Pad5)") (class "Default")
      (node (ref "U7") (pin "5") (pinfunction "USB_DM_5") (pintype "bidirectional"))
    )
    (net (code "94") (name "unconnected-(U7-USB_DP-Pad6)") (class "Default")
      (node (ref "U7") (pin "6") (pinfunction "USB_DP_6") (pintype "bidirectional"))
    )
    (net (code "95") (name "unconnected-(U7-VCC_RF-Pad9)") (class "Default")
      (node (ref "U7") (pin "9") (pinfunction "VCC_RF_9") (pintype "input"))
    )
    (net (code "96") (name "unconnected-(U7-~{RESET}-Pad8)") (class "Default")
      (node (ref "U7") (pin "8") (pinfunction "~{RESET}_8") (pintype "input"))
    )
  )
)
